# LTE_SARA-R422-00B.net
KiCad netlist of a schematic drawn in Altium Designer
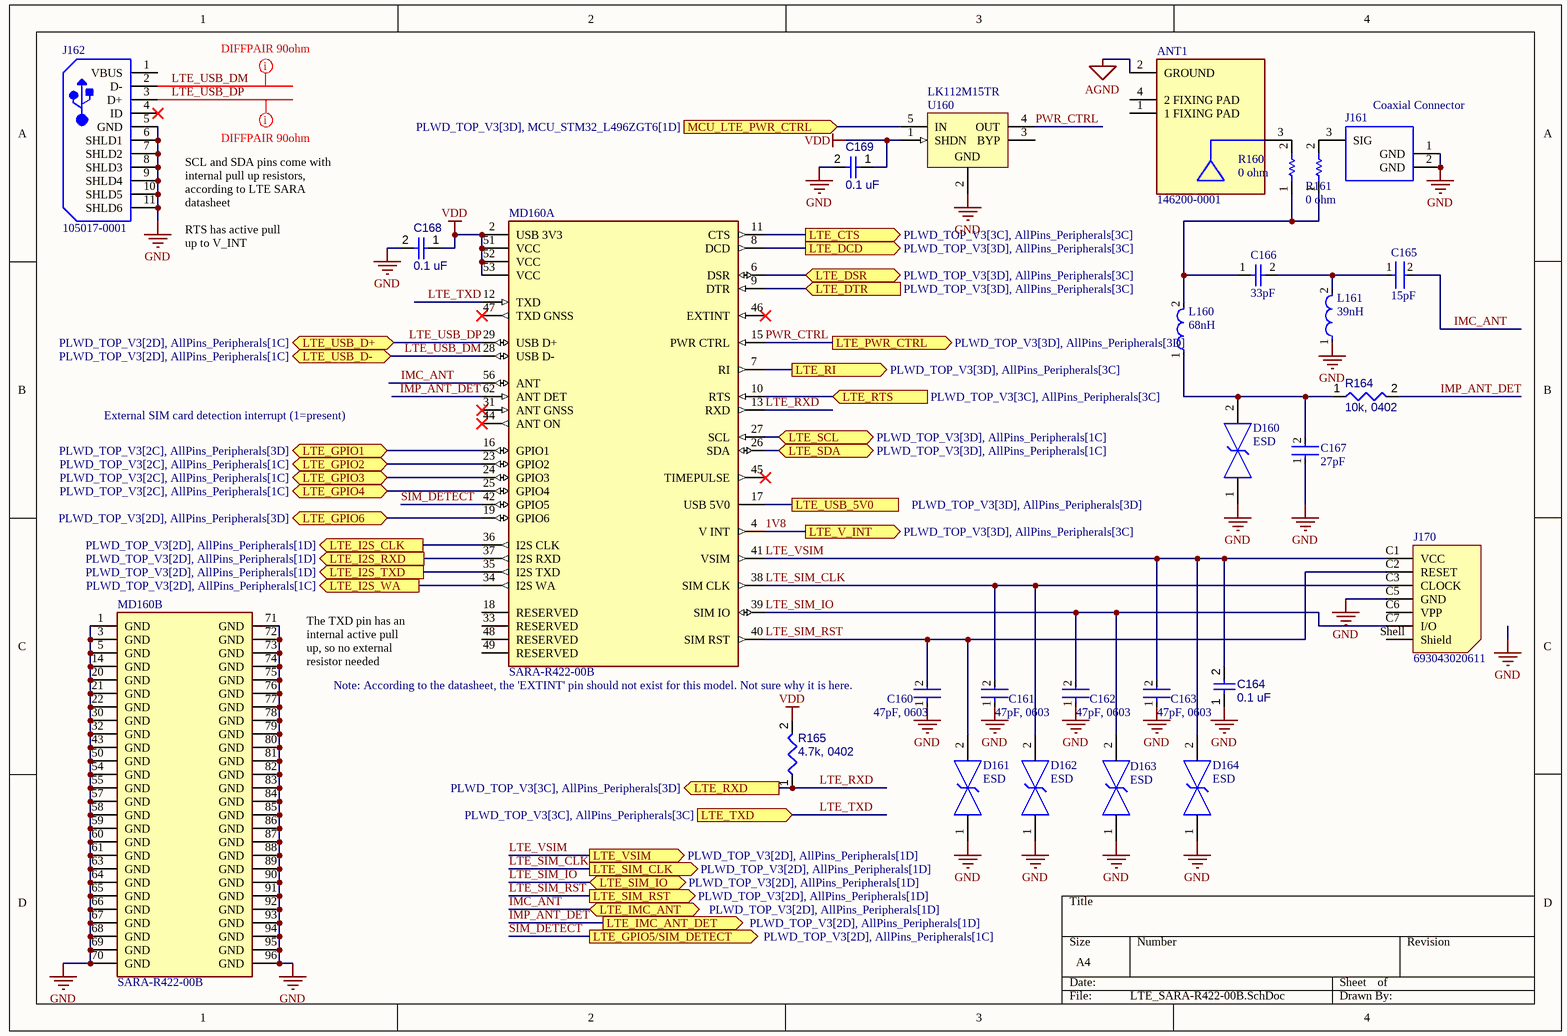
[diagram p0: LTE_SARA-R422-00B.SchDoc]

(export (version "E")
  (design (tool "Eeschema 10.0.6"))
  (components
    (comp (ref "ANT1")
      (value "146200-0001")
      (footprint "FP-146200-0001-MFG")
      (description "RF ANT 829MHZ/2.2GHZ CHIP SLD")
      (fields
        (field (name "MANUFACTURER") "Molex")
        (field (name "OCTOPART") "https://octopart.com/146200-0001-molex-75347041")
      )
      (libsource (lib "Altium Content Vault") (part "7d8c0c348ed51543227e5b4cad97b86"))
    )
    (comp (ref "C160")
      (value "47pF, 0603")
      (footprint "FP-C0603C-CF-MFG")
      (description "CAP CER 47PF 100V 5% NP0")
      (fields
        (field (name "MANUFACTURER") "KEMET")
        (field (name "OCTOPART") "https://octopart.com/c0603c470j1gactu-kemet-3768219")
      )
      (libsource (lib "Altium Content Vault") (part "b4654b650e69147ec39a6b967a45e02"))
    )
    (comp (ref "C161")
      (value "47pF, 0603")
      (footprint "FP-C0603C-CF-MFG")
      (description "CAP CER 47PF 100V 5% NP0")
      (fields
        (field (name "MANUFACTURER") "KEMET")
        (field (name "OCTOPART") "https://octopart.com/c0603c470j1gactu-kemet-3768219")
      )
      (libsource (lib "Altium Content Vault") (part "b4654b650e69147ec39a6b967a45e02"))
    )
    (comp (ref "C162")
      (value "47pF, 0603")
      (footprint "FP-C0603C-CF-MFG")
      (description "CAP CER 47PF 100V 5% NP0")
      (fields
        (field (name "MANUFACTURER") "KEMET")
        (field (name "OCTOPART") "https://octopart.com/c0603c470j1gactu-kemet-3768219")
      )
      (libsource (lib "Altium Content Vault") (part "b4654b650e69147ec39a6b967a45e02"))
    )
    (comp (ref "C163")
      (value "47pF, 0603")
      (footprint "FP-C0603C-CF-MFG")
      (description "CAP CER 47PF 100V 5% NP0")
      (fields
        (field (name "MANUFACTURER") "KEMET")
        (field (name "OCTOPART") "https://octopart.com/c0603c470j1gactu-kemet-3768219")
      )
      (libsource (lib "Altium Content Vault") (part "b4654b650e69147ec39a6b967a45e02"))
    )
    (comp (ref "C164")
      (value "0.1 uF")
      (footprint "CAPC1005X56X25LL10T15")
      (description "Chip Capacitor, 0.1 uF, +/- 5%, 16 V, 0402 (1005 Metric)")
      (fields (field (name "TOLERANCE") "5%"))
      (libsource (lib "Carleton University") (part "CAP-NP-2"))
    )
    (comp (ref "C165")
      (value "15pF")
      (footprint "FP-0603-L_1_6_0_15-W_0_81-IPC_B")
      (description "General Purpose Ceramic Capacitor, 0603, 15pF, 1%, NP0, 30ppm/°C, 50V")
      (fields (field (name "TOLERANCE") "1%"))
      (libsource (lib "Altium Content Vault") (part "02cd4be3c70576c341d710602a673aa"))
    )
    (comp (ref "C166")
      (value "33pF")
      (footprint "CAPC1608X90X35NL15T15")
      (fields
        (field (name "MANUFACTURER") "AVX Interconnect / Elco")
        (field (name "PART NUMBER") "06031A330FAT2A")
      )
      (libsource (lib "Altium Content Vault") (part "CAP"))
    )
    (comp (ref "C167")
      (value "27pF")
      (footprint "FP-C0603C-CF-MFG")
      (description "CAP CER 27PF 50V 1% NP0 0603")
      (fields (field (name "TOLERANCE") "0.01") (field (name "MANUFACTURER") "KEMET"))
      (libsource (lib "Altium Content Vault") (part "b4654b650e69147ec39a6b967a45e02"))
    )
    (comp (ref "C168")
      (value "0.1 uF")
      (footprint "CAPC1005X56X25LL10T15")
      (description "Chip Capacitor, 0.1 uF, +/- 5%, 16 V, 0402 (1005 Metric)")
      (fields (field (name "TOLERANCE") "5%"))
      (libsource (lib "Carleton University") (part "CAP-NP-2"))
    )
    (comp (ref "C169")
      (value "0.1 uF")
      (footprint "CAPC1005X56X25LL10T15")
      (description "Chip Capacitor, 0.1 uF, +/- 5%, 16 V, 0402 (1005 Metric)")
      (fields (field (name "TOLERANCE") "5%"))
      (libsource (lib "Carleton University") (part "CAP-NP-2"))
    )
    (comp (ref "D160")
      (value "ESD")
      (footprint "FP-PG-TSSLP-2-MFG")
      (description "TVS DIODE 5.5V 30V TSSLP-2-4")
      (libsource (lib "Altium Content Vault") (part "65ca83a353309b1d47b4a5f467fa9dd"))
    )
    (comp (ref "D161")
      (value "ESD")
      (footprint "FP-PG-TSSLP-2-MFG")
      (description "TVS DIODE 5.5V 30V TSSLP-2-4")
      (libsource (lib "Altium Content Vault") (part "65ca83a353309b1d47b4a5f467fa9dd"))
    )
    (comp (ref "D162")
      (value "ESD")
      (footprint "FP-PG-TSSLP-2-MFG")
      (description "TVS DIODE 5.5V 30V TSSLP-2-4")
      (libsource (lib "Altium Content Vault") (part "65ca83a353309b1d47b4a5f467fa9dd"))
    )
    (comp (ref "D163")
      (value "ESD")
      (footprint "FP-PG-TSSLP-2-MFG")
      (description "TVS DIODE 5.5V 30V TSSLP-2-4")
      (libsource (lib "Altium Content Vault") (part "65ca83a353309b1d47b4a5f467fa9dd"))
    )
    (comp (ref "D164")
      (value "ESD")
      (footprint "FP-PG-TSSLP-2-MFG")
      (description "TVS DIODE 5.5V 30V TSSLP-2-4")
      (libsource (lib "Altium Content Vault") (part "65ca83a353309b1d47b4a5f467fa9dd"))
    )
    (comp (ref "J161")
      (value "Coaxial Connector")
      (footprint "HRS-U.FL-R-SMT_V")
      (fields (field (name "MANUFACTURER") "Hirose Electric"))
      (libsource (lib "Carleton University") (part "HRS-U.FL-R-SMT-3"))
    )
    (comp (ref "J162")
      (value "105017-0001")
      (footprint "USB-MICRO-B_V")
      (fields (field (name "MANUFACTURER") "Molex"))
      (libsource (lib "Altium Content Vault") (part "USB-5-6SHLD"))
    )
    (comp (ref "J170")
      (value "693043020611")
      (footprint "693043020611")
      (libsource (lib "Altium Content Vault") (part "693043020611"))
    )
    (comp (ref "L160")
      (value "68nH")
      (footprint "FP-LQW18AN_00-MFG")
      (description "Wire Wound RF Inductor 68nH ±2% 340mA 0.38Ω 0603 (1608)")
      (fields (field (name "TOLERANCE") "2%"))
      (libsource (lib "Altium Content Vault") (part "725321dda6339637d4d059423bc1c3c"))
    )
    (comp (ref "L161")
      (value "39nH")
      (footprint "FP-LQW18AN_00-MFG")
      (description "Wire Wound RF Inductor 39nH ±2% 400mA 0.26Ω 0603 (1608)")
      (fields (field (name "TOLERANCE") "2%"))
      (libsource (lib "Altium Content Vault") (part "725321dda6339637d4d059423bc1c3c"))
    )
    (comp (ref "MD160")
      (value "SARA-R422-00B")
      (footprint "FP-SARA-R422-00B-MFG")
      (description "RF TXRX CELL 4G LTE NB-IOT EGPRS")
      (libsource (lib "Altium Content Vault") (part "a1f6eddb185d218fbdc3dc45a4e0f7b"))
    )
    (comp (ref "R160")
      (value "0 ohm")
      (footprint "RESC1005X40X25LL05T10")
      (fields (field (name "MANUFACTURER") "Panasonic") (field (name "PART NUMBER") "ERJ-S020R00X"))
      (libsource (lib "Altium Content Vault") (part "RES"))
    )
    (comp (ref "R161")
      (value "0 ohm")
      (footprint "RESC1005X40X25LL05T10")
      (fields (field (name "MANUFACTURER") "Panasonic") (field (name "PART NUMBER") "ERJ-S020R00X"))
      (libsource (lib "Altium Content Vault") (part "RES"))
    )
    (comp (ref "R164")
      (value "10k, 0402")
      (footprint "RESC1005X40X25ML05T05")
      (description "Chip Resistor, 10 KOhm, +/- 1%, 0.1 W, -55 to 155 degC, 0402 (1005 Metric)")
      (fields (field (name "TOLERANCE") "1%") (field (name "POWER") "100mW"))
      (libsource (lib "Carleton University") (part "RES-2"))
    )
    (comp (ref "R165")
      (value "4.7k, 0402")
      (footprint "RESC0402(1005)_L")
      (description "Chip Resistor, 4,7 kOhms, +/-1 %, 63 mW, -55 to 155 degC, 0402")
      (fields (field (name "POWER") "63mW") (field (name "TOLERANCE") "1%"))
      (libsource (lib "Carleton University") (part "RES-2"))
    )
    (comp (ref "U160")
      (value "LK112M15TR")
      (footprint "SOT23-5L_L")
      (description "Low Noise Low Drop Voltage Regulator with Shutdown Function, 1.5V, 5-Pin SOT23-5L, Tape and Reel")
      (libsource (lib "Altium Content Vault") (part "PM-REG-LK112M-SOT5"))
    )
  )
  (nets
    (net (code "1") (name "/1V8") (class "Default")
      (node (ref "MD160") (pin "4") (pinfunction "V_INT_4") (pintype "output"))
    )
    (net (code "2") (name "/IMC_ANT") (class "Default")
      (node (ref "C165") (pin "2") (pinfunction "2_2") (pintype "passive"))
      (node (ref "MD160") (pin "56") (pinfunction "ANT_56") (pintype "bidirectional"))
    )
    (net (code "3") (name "/IMP_ANT_DET") (class "Default")
      (node (ref "MD160") (pin "62") (pinfunction "ANT_DET_62") (pintype "input"))
      (node (ref "R164") (pin "2") (pinfunction "2_2") (pintype "passive"))
    )
    (net (code "4") (name "/LTE_CTS") (class "Default")
      (node (ref "MD160") (pin "11") (pinfunction "CTS_11") (pintype "output"))
    )
    (net (code "5") (name "/LTE_DCD") (class "Default")
      (node (ref "MD160") (pin "8") (pinfunction "DCD_8") (pintype "output"))
    )
    (net (code "6") (name "/LTE_DSR") (class "Default")
      (node (ref "MD160") (pin "6") (pinfunction "DSR_6") (pintype "bidirectional"))
    )
    (net (code "7") (name "/LTE_DTR") (class "Default")
      (node (ref "MD160") (pin "9") (pinfunction "DTR_9") (pintype "input"))
    )
    (net (code "8") (name "/LTE_GPIO1") (class "Default")
      (node (ref "MD160") (pin "16") (pinfunction "GPIO1_16") (pintype "bidirectional"))
    )
    (net (code "9") (name "/LTE_GPIO2") (class "Default")
      (node (ref "MD160") (pin "23") (pinfunction "GPIO2_23") (pintype "bidirectional"))
    )
    (net (code "10") (name "/LTE_GPIO3") (class "Default")
      (node (ref "MD160") (pin "24") (pinfunction "GPIO3_24") (pintype "bidirectional"))
    )
    (net (code "11") (name "/LTE_GPIO4") (class "Default")
      (node (ref "MD160") (pin "25") (pinfunction "GPIO4_25") (pintype "bidirectional"))
    )
    (net (code "12") (name "/LTE_GPIO6") (class "Default")
      (node (ref "MD160") (pin "19") (pinfunction "GPIO6_19") (pintype "bidirectional"))
    )
    (net (code "13") (name "/LTE_I2S_CLK") (class "Default")
      (node (ref "MD160") (pin "36") (pinfunction "I2S_CLK_36") (pintype "output"))
    )
    (net (code "14") (name "/LTE_I2S_RXD") (class "Default")
      (node (ref "MD160") (pin "37") (pinfunction "I2S_RXD_37") (pintype "output"))
    )
    (net (code "15") (name "/LTE_I2S_TXD") (class "Default")
      (node (ref "MD160") (pin "35") (pinfunction "I2S_TXD_35") (pintype "output"))
    )
    (net (code "16") (name "/LTE_I2S_WA") (class "Default")
      (node (ref "MD160") (pin "34") (pinfunction "I2S_WA_34") (pintype "output"))
    )
    (net (code "17") (name "/LTE_RI") (class "Default")
      (node (ref "MD160") (pin "7") (pinfunction "RI_7") (pintype "output"))
    )
    (net (code "18") (name "/LTE_RTS") (class "Default")
      (node (ref "MD160") (pin "10") (pinfunction "RTS_10") (pintype "input"))
    )
    (net (code "19") (name "/LTE_RXD") (class "Default")
      (node (ref "MD160") (pin "13") (pinfunction "RXD_13") (pintype "output"))
      (node (ref "R165") (pin "1") (pinfunction "1_1") (pintype "passive"))
    )
    (net (code "20") (name "/LTE_SCL") (class "Default")
      (node (ref "MD160") (pin "27") (pinfunction "SCL_27") (pintype "input"))
    )
    (net (code "21") (name "/LTE_SDA") (class "Default")
      (node (ref "MD160") (pin "26") (pinfunction "SDA_26") (pintype "bidirectional"))
    )
    (net (code "22") (name "/LTE_SIM_CLK") (class "Default")
      (node (ref "C161") (pin "2") (pinfunction "2_2") (pintype "passive"))
      (node (ref "D162") (pin "2") (pinfunction "2_2") (pintype "passive"))
      (node (ref "J170") (pin "C3") (pinfunction "CLOCK_C3") (pintype "passive"))
      (node (ref "MD160") (pin "38") (pinfunction "SIM_CLK_38") (pintype "output"))
    )
    (net (code "23") (name "/LTE_SIM_IO") (class "Default")
      (node (ref "C162") (pin "2") (pinfunction "2_2") (pintype "passive"))
      (node (ref "D163") (pin "2") (pinfunction "2_2") (pintype "passive"))
      (node (ref "J170") (pin "C7") (pinfunction "I/O_C7") (pintype "passive"))
      (node (ref "MD160") (pin "39") (pinfunction "SIM_IO_39") (pintype "bidirectional"))
    )
    (net (code "24") (name "/LTE_SIM_RST") (class "Default")
      (node (ref "C160") (pin "2") (pinfunction "2_2") (pintype "passive"))
      (node (ref "D161") (pin "2") (pinfunction "2_2") (pintype "passive"))
      (node (ref "J170") (pin "C2") (pinfunction "RESET_C2") (pintype "passive"))
      (node (ref "MD160") (pin "40") (pinfunction "SIM_RST_40") (pintype "output"))
    )
    (net (code "25") (name "/LTE_TXD") (class "Default")
      (node (ref "MD160") (pin "12") (pinfunction "TXD_12") (pintype "input"))
    )
    (net (code "26") (name "/LTE_USB_5V0") (class "Default")
      (node (ref "MD160") (pin "17") (pinfunction "USB_5V0_17") (pintype "power_in"))
    )
    (net (code "27") (name "/LTE_USB_DM") (class "Default")
      (node (ref "J162") (pin "2") (pinfunction "D-_2") (pintype "passive"))
      (node (ref "MD160") (pin "28") (pinfunction "USB_D-_28") (pintype "bidirectional"))
    )
    (net (code "28") (name "/LTE_USB_DP") (class "Default")
      (node (ref "J162") (pin "3") (pinfunction "D+_3") (pintype "passive"))
      (node (ref "MD160") (pin "29") (pinfunction "USB_D+_29") (pintype "bidirectional"))
    )
    (net (code "29") (name "/LTE_VSIM") (class "Default")
      (node (ref "C163") (pin "2") (pinfunction "2_2") (pintype "passive"))
      (node (ref "C164") (pin "2") (pinfunction "2_2") (pintype "passive"))
      (node (ref "D164") (pin "2") (pinfunction "2_2") (pintype "passive"))
      (node (ref "J170") (pin "C1") (pinfunction "VCC_C1") (pintype "passive"))
      (node (ref "MD160") (pin "41") (pinfunction "VSIM_41") (pintype "output"))
    )
    (net (code "30") (name "/MCU_LTE_PWR_CTRL") (class "Default")
      (node (ref "U160") (pin "5") (pinfunction "IN_5") (pintype "power_in"))
    )
    (net (code "31") (name "/PWR_CTRL") (class "Default")
      (node (ref "MD160") (pin "15") (pinfunction "PWR_CTRL_15") (pintype "input"))
      (node (ref "U160") (pin "4") (pinfunction "OUT_4") (pintype "power_in"))
    )
    (net (code "32") (name "/SIM_DETECT") (class "Default")
      (node (ref "MD160") (pin "42") (pinfunction "GPIO5_42") (pintype "bidirectional"))
    )
    (net (code "33") (name "AGND") (class "Default")
      (node (ref "ANT1") (pin "2") (pinfunction "GROUND_2") (pintype "power_in"))
    )
    (net (code "34") (name "GND") (class "Default")
      (node (ref "C160") (pin "1") (pinfunction "1_1") (pintype "passive"))
      (node (ref "C161") (pin "1") (pinfunction "1_1") (pintype "passive"))
      (node (ref "C162") (pin "1") (pinfunction "1_1") (pintype "passive"))
      (node (ref "C163") (pin "1") (pinfunction "1_1") (pintype "passive"))
      (node (ref "C164") (pin "1") (pinfunction "1_1") (pintype "passive"))
      (node (ref "C167") (pin "1") (pinfunction "1_1") (pintype "passive"))
      (node (ref "C168") (pin "2") (pinfunction "2_2") (pintype "passive"))
      (node (ref "C169") (pin "2") (pinfunction "2_2") (pintype "passive"))
      (node (ref "D160") (pin "1") (pinfunction "1_1") (pintype "passive"))
      (node (ref "D161") (pin "1") (pinfunction "1_1") (pintype "passive"))
      (node (ref "D162") (pin "1") (pinfunction "1_1") (pintype "passive"))
      (node (ref "D163") (pin "1") (pinfunction "1_1") (pintype "passive"))
      (node (ref "D164") (pin "1") (pinfunction "1_1") (pintype "passive"))
      (node (ref "J161") (pin "1") (pinfunction "GND_1") (pintype "power_in"))
      (node (ref "J161") (pin "2") (pinfunction "GND_2") (pintype "power_in"))
      (node (ref "J162") (pin "10") (pinfunction "SHLD5_10") (pintype "passive"))
      (node (ref "J162") (pin "11") (pinfunction "SHLD6_11") (pintype "passive"))
      (node (ref "J162") (pin "5") (pinfunction "GND_5") (pintype "passive"))
      (node (ref "J162") (pin "6") (pinfunction "SHLD1_6") (pintype "passive"))
      (node (ref "J162") (pin "7") (pinfunction "SHLD2_7") (pintype "passive"))
      (node (ref "J162") (pin "8") (pinfunction "SHLD3_8") (pintype "passive"))
      (node (ref "J162") (pin "9") (pinfunction "SHLD4_9") (pintype "passive"))
      (node (ref "J170") (pin "C5") (pinfunction "GND_C5") (pintype "passive"))
      (node (ref "L161") (pin "1") (pinfunction "1_1") (pintype "passive"))
      (node (ref "MD160") (pin "1") (pinfunction "GND_1") (pintype "power_in"))
      (node (ref "MD160") (pin "14") (pinfunction "GND_14") (pintype "power_in"))
      (node (ref "MD160") (pin "20") (pinfunction "GND_20") (pintype "power_in"))
      (node (ref "MD160") (pin "21") (pinfunction "GND_21") (pintype "power_in"))
      (node (ref "MD160") (pin "22") (pinfunction "GND_22") (pintype "power_in"))
      (node (ref "MD160") (pin "3") (pinfunction "GND_3") (pintype "power_in"))
      (node (ref "MD160") (pin "30") (pinfunction "GND_30") (pintype "power_in"))
      (node (ref "MD160") (pin "32") (pinfunction "GND_32") (pintype "power_in"))
      (node (ref "MD160") (pin "43") (pinfunction "GND_43") (pintype "power_in"))
      (node (ref "MD160") (pin "5") (pinfunction "GND_5") (pintype "power_in"))
      (node (ref "MD160") (pin "50") (pinfunction "GND_50") (pintype "power_in"))
      (node (ref "MD160") (pin "54") (pinfunction "GND_54") (pintype "power_in"))
      (node (ref "MD160") (pin "55") (pinfunction "GND_55") (pintype "power_in"))
      (node (ref "MD160") (pin "57") (pinfunction "GND_57") (pintype "power_in"))
      (node (ref "MD160") (pin "58") (pinfunction "GND_58") (pintype "power_in"))
      (node (ref "MD160") (pin "59") (pinfunction "GND_59") (pintype "power_in"))
      (node (ref "MD160") (pin "60") (pinfunction "GND_60") (pintype "power_in"))
      (node (ref "MD160") (pin "61") (pinfunction "GND_61") (pintype "power_in"))
      (node (ref "MD160") (pin "63") (pinfunction "GND_63") (pintype "power_in"))
      (node (ref "MD160") (pin "64") (pinfunction "GND_64") (pintype "power_in"))
      (node (ref "MD160") (pin "65") (pinfunction "GND_65") (pintype "power_in"))
      (node (ref "MD160") (pin "66") (pinfunction "GND_66") (pintype "power_in"))
      (node (ref "MD160") (pin "67") (pinfunction "GND_67") (pintype "power_in"))
      (node (ref "MD160") (pin "68") (pinfunction "GND_68") (pintype "power_in"))
      (node (ref "MD160") (pin "69") (pinfunction "GND_69") (pintype "power_in"))
      (node (ref "MD160") (pin "70") (pinfunction "GND_70") (pintype "power_in"))
      (node (ref "MD160") (pin "71") (pinfunction "GND_71") (pintype "power_in"))
      (node (ref "MD160") (pin "72") (pinfunction "GND_72") (pintype "power_in"))
      (node (ref "MD160") (pin "73") (pinfunction "GND_73") (pintype "power_in"))
      (node (ref "MD160") (pin "74") (pinfunction "GND_74") (pintype "power_in"))
      (node (ref "MD160") (pin "75") (pinfunction "GND_75") (pintype "power_in"))
      (node (ref "MD160") (pin "76") (pinfunction "GND_76") (pintype "power_in"))
      (node (ref "MD160") (pin "77") (pinfunction "GND_77") (pintype "power_in"))
      (node (ref "MD160") (pin "78") (pinfunction "GND_78") (pintype "power_in"))
      (node (ref "MD160") (pin "79") (pinfunction "GND_79") (pintype "power_in"))
      (node (ref "MD160") (pin "80") (pinfunction "GND_80") (pintype "power_in"))
      (node (ref "MD160") (pin "81") (pinfunction "GND_81") (pintype "power_in"))
      (node (ref "MD160") (pin "82") (pinfunction "GND_82") (pintype "power_in"))
      (node (ref "MD160") (pin "83") (pinfunction "GND_83") (pintype "power_in"))
      (node (ref "MD160") (pin "84") (pinfunction "GND_84") (pintype "power_in"))
      (node (ref "MD160") (pin "85") (pinfunction "GND_85") (pintype "power_in"))
      (node (ref "MD160") (pin "86") (pinfunction "GND_86") (pintype "power_in"))
      (node (ref "MD160") (pin "87") (pinfunction "GND_87") (pintype "power_in"))
      (node (ref "MD160") (pin "88") (pinfunction "GND_88") (pintype "power_in"))
      (node (ref "MD160") (pin "89") (pinfunction "GND_89") (pintype "power_in"))
      (node (ref "MD160") (pin "90") (pinfunction "GND_90") (pintype "power_in"))
      (node (ref "MD160") (pin "91") (pinfunction "GND_91") (pintype "power_in"))
      (node (ref "MD160") (pin "92") (pinfunction "GND_92") (pintype "power_in"))
      (node (ref "MD160") (pin "93") (pinfunction "GND_93") (pintype "power_in"))
      (node (ref "MD160") (pin "94") (pinfunction "GND_94") (pintype "power_in"))
      (node (ref "MD160") (pin "95") (pinfunction "GND_95") (pintype "power_in"))
      (node (ref "MD160") (pin "96") (pinfunction "GND_96") (pintype "power_in"))
      (node (ref "U160") (pin "2") (pinfunction "GND_2") (pintype "power_in"))
    )
    (net (code "35") (name "Net-(ANT1-FEEDING)") (class "Default")
      (node (ref "ANT1") (pin "3") (pinfunction "FEEDING_3") (pintype "passive"))
      (node (ref "R160") (pin "2") (pinfunction "2_2") (pintype "passive"))
    )
    (net (code "36") (name "Net-(C165-Pad1)") (class "Default")
      (node (ref "C165") (pin "1") (pinfunction "1_1") (pintype "passive"))
      (node (ref "C166") (pin "2") (pinfunction "2_2") (pintype "passive"))
      (node (ref "L161") (pin "2") (pinfunction "2_2") (pintype "passive"))
    )
    (net (code "37") (name "Net-(C166-Pad1)") (class "Default")
      (node (ref "C166") (pin "1") (pinfunction "1_1") (pintype "passive"))
      (node (ref "L160") (pin "2") (pinfunction "2_2") (pintype "passive"))
      (node (ref "R160") (pin "1") (pinfunction "1_1") (pintype "passive"))
      (node (ref "R161") (pin "1") (pinfunction "1_1") (pintype "passive"))
    )
    (net (code "38") (name "Net-(C167-Pad2)") (class "Default")
      (node (ref "C167") (pin "2") (pinfunction "2_2") (pintype "passive"))
      (node (ref "D160") (pin "2") (pinfunction "2_2") (pintype "passive"))
      (node (ref "L160") (pin "1") (pinfunction "1_1") (pintype "passive"))
      (node (ref "R164") (pin "1") (pinfunction "1_1") (pintype "passive"))
    )
    (net (code "39") (name "Net-(J161-SIG)") (class "Default")
      (node (ref "J161") (pin "3") (pinfunction "SIG_3") (pintype "passive"))
      (node (ref "R161") (pin "2") (pinfunction "2_2") (pintype "passive"))
    )
    (net (code "40") (name "VDD") (class "Default")
      (node (ref "C168") (pin "1") (pinfunction "1_1") (pintype "passive"))
      (node (ref "C169") (pin "1") (pinfunction "1_1") (pintype "passive"))
      (node (ref "MD160") (pin "2") (pinfunction "USB_3V3_2") (pintype "power_in"))
      (node (ref "MD160") (pin "51") (pinfunction "VCC_51") (pintype "power_in"))
      (node (ref "MD160") (pin "52") (pinfunction "VCC_52") (pintype "power_in"))
      (node (ref "MD160") (pin "53") (pinfunction "VCC_53") (pintype "power_in"))
      (node (ref "R165") (pin "2") (pinfunction "2_2") (pintype "passive"))
      (node (ref "U160") (pin "1") (pinfunction "SHDN_1") (pintype "input"))
    )
    (net (code "41") (name "unconnected-(ANT1-1_FIXING_PAD-Pad1)") (class "Default")
      (node (ref "ANT1") (pin "1") (pinfunction "1_FIXING_PAD_1") (pintype "passive"))
    )
    (net (code "42") (name "unconnected-(ANT1-2_FIXING_PAD-Pad4)") (class "Default")
      (node (ref "ANT1") (pin "4") (pinfunction "2_FIXING_PAD_4") (pintype "passive"))
    )
    (net (code "43") (name "unconnected-(J162-ID-Pad4)") (class "Default")
      (node (ref "J162") (pin "4") (pinfunction "ID_4") (pintype "passive+no_connect"))
    )
    (net (code "44") (name "unconnected-(J162-VBUS-Pad1)") (class "Default")
      (node (ref "J162") (pin "1") (pinfunction "VBUS_1") (pintype "passive"))
    )
    (net (code "45") (name "unconnected-(J170-Shield-PadShell)") (class "Default")
      (node (ref "J170") (pin "Shell") (pinfunction "Shield_Shell") (pintype "passive"))
    )
    (net (code "46") (name "unconnected-(J170-VPP-PadC6)") (class "Default")
      (node (ref "J170") (pin "C6") (pinfunction "VPP_C6") (pintype "passive"))
    )
    (net (code "47") (name "unconnected-(MD160A-ANT_GNSS-Pad31)") (class "Default")
      (node (ref "MD160") (pin "31") (pinfunction "ANT_GNSS_31") (pintype "input+no_connect"))
    )
    (net (code "48") (name "unconnected-(MD160A-ANT_ON-Pad44)") (class "Default")
      (node (ref "MD160") (pin "44") (pinfunction "ANT_ON_44") (pintype "output+no_connect"))
    )
    (net (code "49") (name "unconnected-(MD160A-EXTINT-Pad46)") (class "Default")
      (node (ref "MD160") (pin "46") (pinfunction "EXTINT_46") (pintype "input+no_connect"))
    )
    (net (code "50") (name "unconnected-(MD160A-RESERVED-Pad18)") (class "Default")
      (node (ref "MD160") (pin "18") (pinfunction "RESERVED_18") (pintype "passive"))
    )
    (net (code "51") (name "unconnected-(MD160A-RESERVED-Pad33)") (class "Default")
      (node (ref "MD160") (pin "33") (pinfunction "RESERVED_33") (pintype "passive"))
    )
    (net (code "52") (name "unconnected-(MD160A-RESERVED-Pad48)") (class "Default")
      (node (ref "MD160") (pin "48") (pinfunction "RESERVED_48") (pintype "passive"))
    )
    (net (code "53") (name "unconnected-(MD160A-RESERVED-Pad49)") (class "Default")
      (node (ref "MD160") (pin "49") (pinfunction "RESERVED_49") (pintype "passive"))
    )
    (net (code "54") (name "unconnected-(MD160A-TIMEPULSE-Pad45)") (class "Default")
      (node (ref "MD160") (pin "45") (pinfunction "TIMEPULSE_45") (pintype "output+no_connect"))
    )
    (net (code "55") (name "unconnected-(MD160A-TXD_GNSS-Pad47)") (class "Default")
      (node (ref "MD160") (pin "47") (pinfunction "TXD_GNSS_47") (pintype "output+no_connect"))
    )
    (net (code "56") (name "unconnected-(U160-BYP-Pad3)") (class "Default")
      (node (ref "U160") (pin "3") (pinfunction "BYP_3") (pintype "passive"))
    )
  )
)
